# CAN.net
KiCad netlist of a schematic drawn in Altium Designer
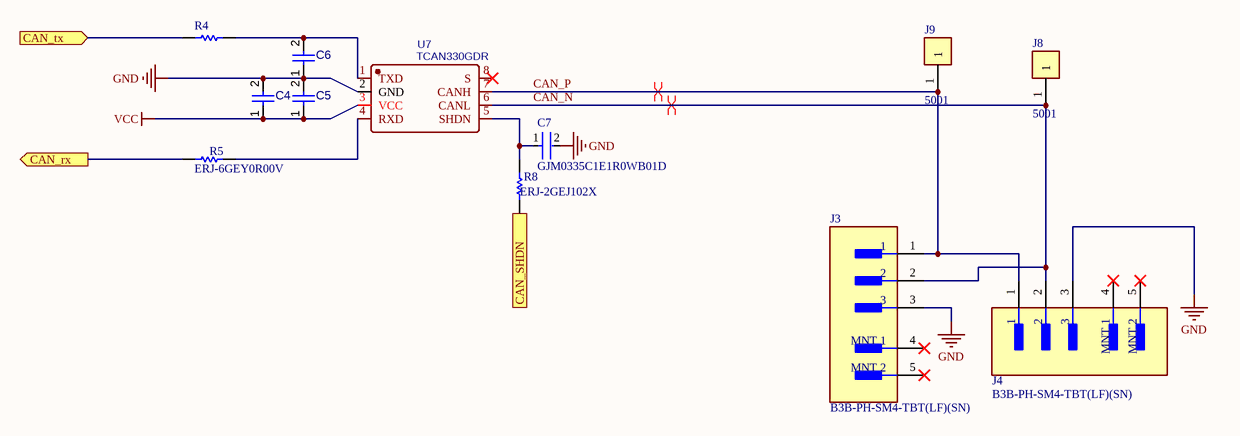
[diagram p0: CAN.SchDoc]

(export (version "E")
  (design (tool "Eeschema 10.0.6"))
  (components
    (comp (ref "C4")
      (value "KGM15CR71C105JT")
      (footprint "CAP-0603")
      (description "Cap Cer 1UF 16V X7R 0603")
      (libsource (lib "University of Michigan") (part "CAP-NP-2"))
    )
    (comp (ref "C5")
      (value "KGM15CR71C105JT")
      (footprint "CAP-0603")
      (description "Cap Cer 1UF 16V X7R 0603")
      (libsource (lib "University of Michigan") (part "CAP-NP-2"))
    )
    (comp (ref "C6")
      (value "KGM15CR71C105JT")
      (footprint "CAP-0603")
      (description "Cap Cer 1UF 16V X7R 0603")
      (libsource (lib "University of Michigan") (part "CAP-NP-2"))
    )
    (comp (ref "C7")
      (value "GJM0335C1E1R0WB01D")
      (footprint "FP-GJM033-0_03-IPC_A")
      (description "Ceramic Capacitor 1pF ±0.05pF 25V C0G 0201 (0603 Metric)")
      (libsource (lib "Altium Content Vault") (part "b4654b650e69147ec39a6b967a45e02"))
    )
    (comp (ref "J3")
      (value "B3B-PH-SM4-TBT(LF)(SN)")
      (footprint "FP-B3B-PH-SM4-TBT_LF_SN-MFG")
      (description "CONN HEADER SMD 3POS 2MM")
      (libsource (lib "Altium Content Vault") (part "38689d6f3df0f9b234c6ddcef280d85"))
    )
    (comp (ref "J4")
      (value "B3B-PH-SM4-TBT(LF)(SN)")
      (footprint "FP-B3B-PH-SM4-TBT_LF_SN-MFG")
      (description "CONN HEADER SMD 3POS 2MM")
      (libsource (lib "") (part "38689d6f3df0f9b234c6ddcef280d85_1"))
    )
    (comp (ref "J8")
      (value "5001")
      (footprint "FP-5001-MFG")
      (description "PC TEST POINT MINIATURE BLACK")
      (libsource (lib "Altium Content Vault") (part "1e4615820a309e3ce90f9e6d957b7fa"))
    )
    (comp (ref "J9")
      (value "5001")
      (footprint "FP-5001-MFG")
      (description "PC TEST POINT MINIATURE BLACK")
      (libsource (lib "Altium Content Vault") (part "1e4615820a309e3ce90f9e6d957b7fa"))
    )
    (comp (ref "R4")
      (value "ERJ-6GEY0R00V")
      (footprint "RESC2013X70X40NL20T20")
      (description "Chip Resistor, 0 Ohm, +/- 1%, 0.125 W, -55 to 155 degC, 0805 (2012 Metric), RoHS, Tape and Reel")
      (fields (field (name "TOLERANCE") "5%"))
      (libsource (lib "Altium Content Vault") (part "RES-2"))
    )
    (comp (ref "R5")
      (value "ERJ-6GEY0R00V")
      (footprint "RESC2013X70X40NL20T20")
      (description "Chip Resistor, 0 Ohm, +/- 1%, 0.125 W, -55 to 155 degC, 0805 (2012 Metric), RoHS, Tape and Reel")
      (fields (field (name "TOLERANCE") "5%"))
      (libsource (lib "Altium Content Vault") (part "RES-2"))
    )
    (comp (ref "R8")
      (value "ERJ-2GEJ102X")
      (footprint "RESC1005X40X25NL05T05")
      (fields (field (name "MANUFACTURER") "Panasonic"))
      (libsource (lib "Altium Content Vault") (part "RES"))
    )
    (comp (ref "U7")
      (value "TCAN330GDR")
      (footprint "MasterLib:IC-BUCK-8SOIC")
      (fields (field (name "BOM_SUPPLIER PART") "C191009") (field (name "CONTRIBUTOR") "LCSC"))
      (libsource (lib "altium-import") (part "root_0_TCAN330GDR_"))
    )
  )
  (nets
    (net (code "1") (name "/CAN_N") (class "Default")
      (node (ref "J3") (pin "2") (pinfunction "2_2") (pintype "passive"))
      (node (ref "J4") (pin "2") (pinfunction "2_2") (pintype "passive"))
      (node (ref "J8") (pin "1") (pinfunction "1_1") (pintype "passive"))
      (node (ref "U7") (pin "6") (pinfunction "CANL_6") (pintype "passive"))
    )
    (net (code "2") (name "/CAN_P") (class "Default")
      (node (ref "J3") (pin "1") (pinfunction "1_1") (pintype "passive"))
      (node (ref "J4") (pin "1") (pinfunction "1_1") (pintype "passive"))
      (node (ref "J9") (pin "1") (pinfunction "1_1") (pintype "passive"))
      (node (ref "U7") (pin "7") (pinfunction "CANH_7") (pintype "passive"))
    )
    (net (code "3") (name "/CAN_SHDN") (class "Default")
      (node (ref "R8") (pin "1") (pinfunction "1_1") (pintype "passive"))
    )
    (net (code "4") (name "/CAN_rx") (class "Default")
      (node (ref "R5") (pin "1") (pinfunction "1_1") (pintype "passive"))
    )
    (net (code "5") (name "/CAN_tx") (class "Default")
      (node (ref "R4") (pin "1") (pinfunction "1_1") (pintype "passive"))
    )
    (net (code "6") (name "GND") (class "Default")
      (node (ref "C4") (pin "2") (pinfunction "2_2") (pintype "passive"))
      (node (ref "C5") (pin "2") (pinfunction "2_2") (pintype "passive"))
      (node (ref "C6") (pin "1") (pinfunction "1_1") (pintype "passive"))
      (node (ref "C7") (pin "2") (pinfunction "2_2") (pintype "passive"))
      (node (ref "J3") (pin "3") (pinfunction "3_3") (pintype "passive"))
      (node (ref "J4") (pin "3") (pinfunction "3_3") (pintype "passive"))
      (node (ref "U7") (pin "2") (pinfunction "GND_2") (pintype "passive"))
    )
    (net (code "7") (name "Net-(U7-RXD)") (class "Default")
      (node (ref "R5") (pin "2") (pinfunction "2_2") (pintype "passive"))
      (node (ref "U7") (pin "4") (pinfunction "RXD_4") (pintype "passive"))
    )
    (net (code "8") (name "Net-(U7-SHDN)") (class "Default")
      (node (ref "C7") (pin "1") (pinfunction "1_1") (pintype "passive"))
      (node (ref "R8") (pin "2") (pinfunction "2_2") (pintype "passive"))
      (node (ref "U7") (pin "5") (pinfunction "SHDN_5") (pintype "passive"))
    )
    (net (code "9") (name "Net-(U7-TXD)") (class "Default")
      (node (ref "C6") (pin "2") (pinfunction "2_2") (pintype "passive"))
      (node (ref "R4") (pin "2") (pinfunction "2_2") (pintype "passive"))
      (node (ref "U7") (pin "1") (pinfunction "TXD_1") (pintype "passive"))
    )
    (net (code "10") (name "VCC") (class "Default")
      (node (ref "C4") (pin "1") (pinfunction "1_1") (pintype "passive"))
      (node (ref "C5") (pin "1") (pinfunction "1_1") (pintype "passive"))
      (node (ref "U7") (pin "3") (pinfunction "VCC_3") (pintype "passive"))
    )
    (net (code "11") (name "unconnected-(J3-MNT_1-Pad4)") (class "Default")
      (node (ref "J3") (pin "4") (pinfunction "MNT_1_4") (pintype "passive+no_connect"))
    )
    (net (code "12") (name "unconnected-(J3-MNT_2-Pad5)") (class "Default")
      (node (ref "J3") (pin "5") (pinfunction "MNT_2_5") (pintype "passive+no_connect"))
    )
    (net (code "13") (name "unconnected-(J4-MNT_1-Pad4)") (class "Default")
      (node (ref "J4") (pin "4") (pinfunction "MNT_1_4") (pintype "passive+no_connect"))
    )
    (net (code "14") (name "unconnected-(J4-MNT_2-Pad5)") (class "Default")
      (node (ref "J4") (pin "5") (pinfunction "MNT_2_5") (pintype "passive+no_connect"))
    )
    (net (code "15") (name "unconnected-(U7-S-Pad8)") (class "Default")
      (node (ref "U7") (pin "8") (pinfunction "S_8") (pintype "passive+no_connect"))
    )
  )
)
